# Spring_Schematic_r1_1_easyeda.net
KiCad netlist of a schematic drawn in EasyEDA
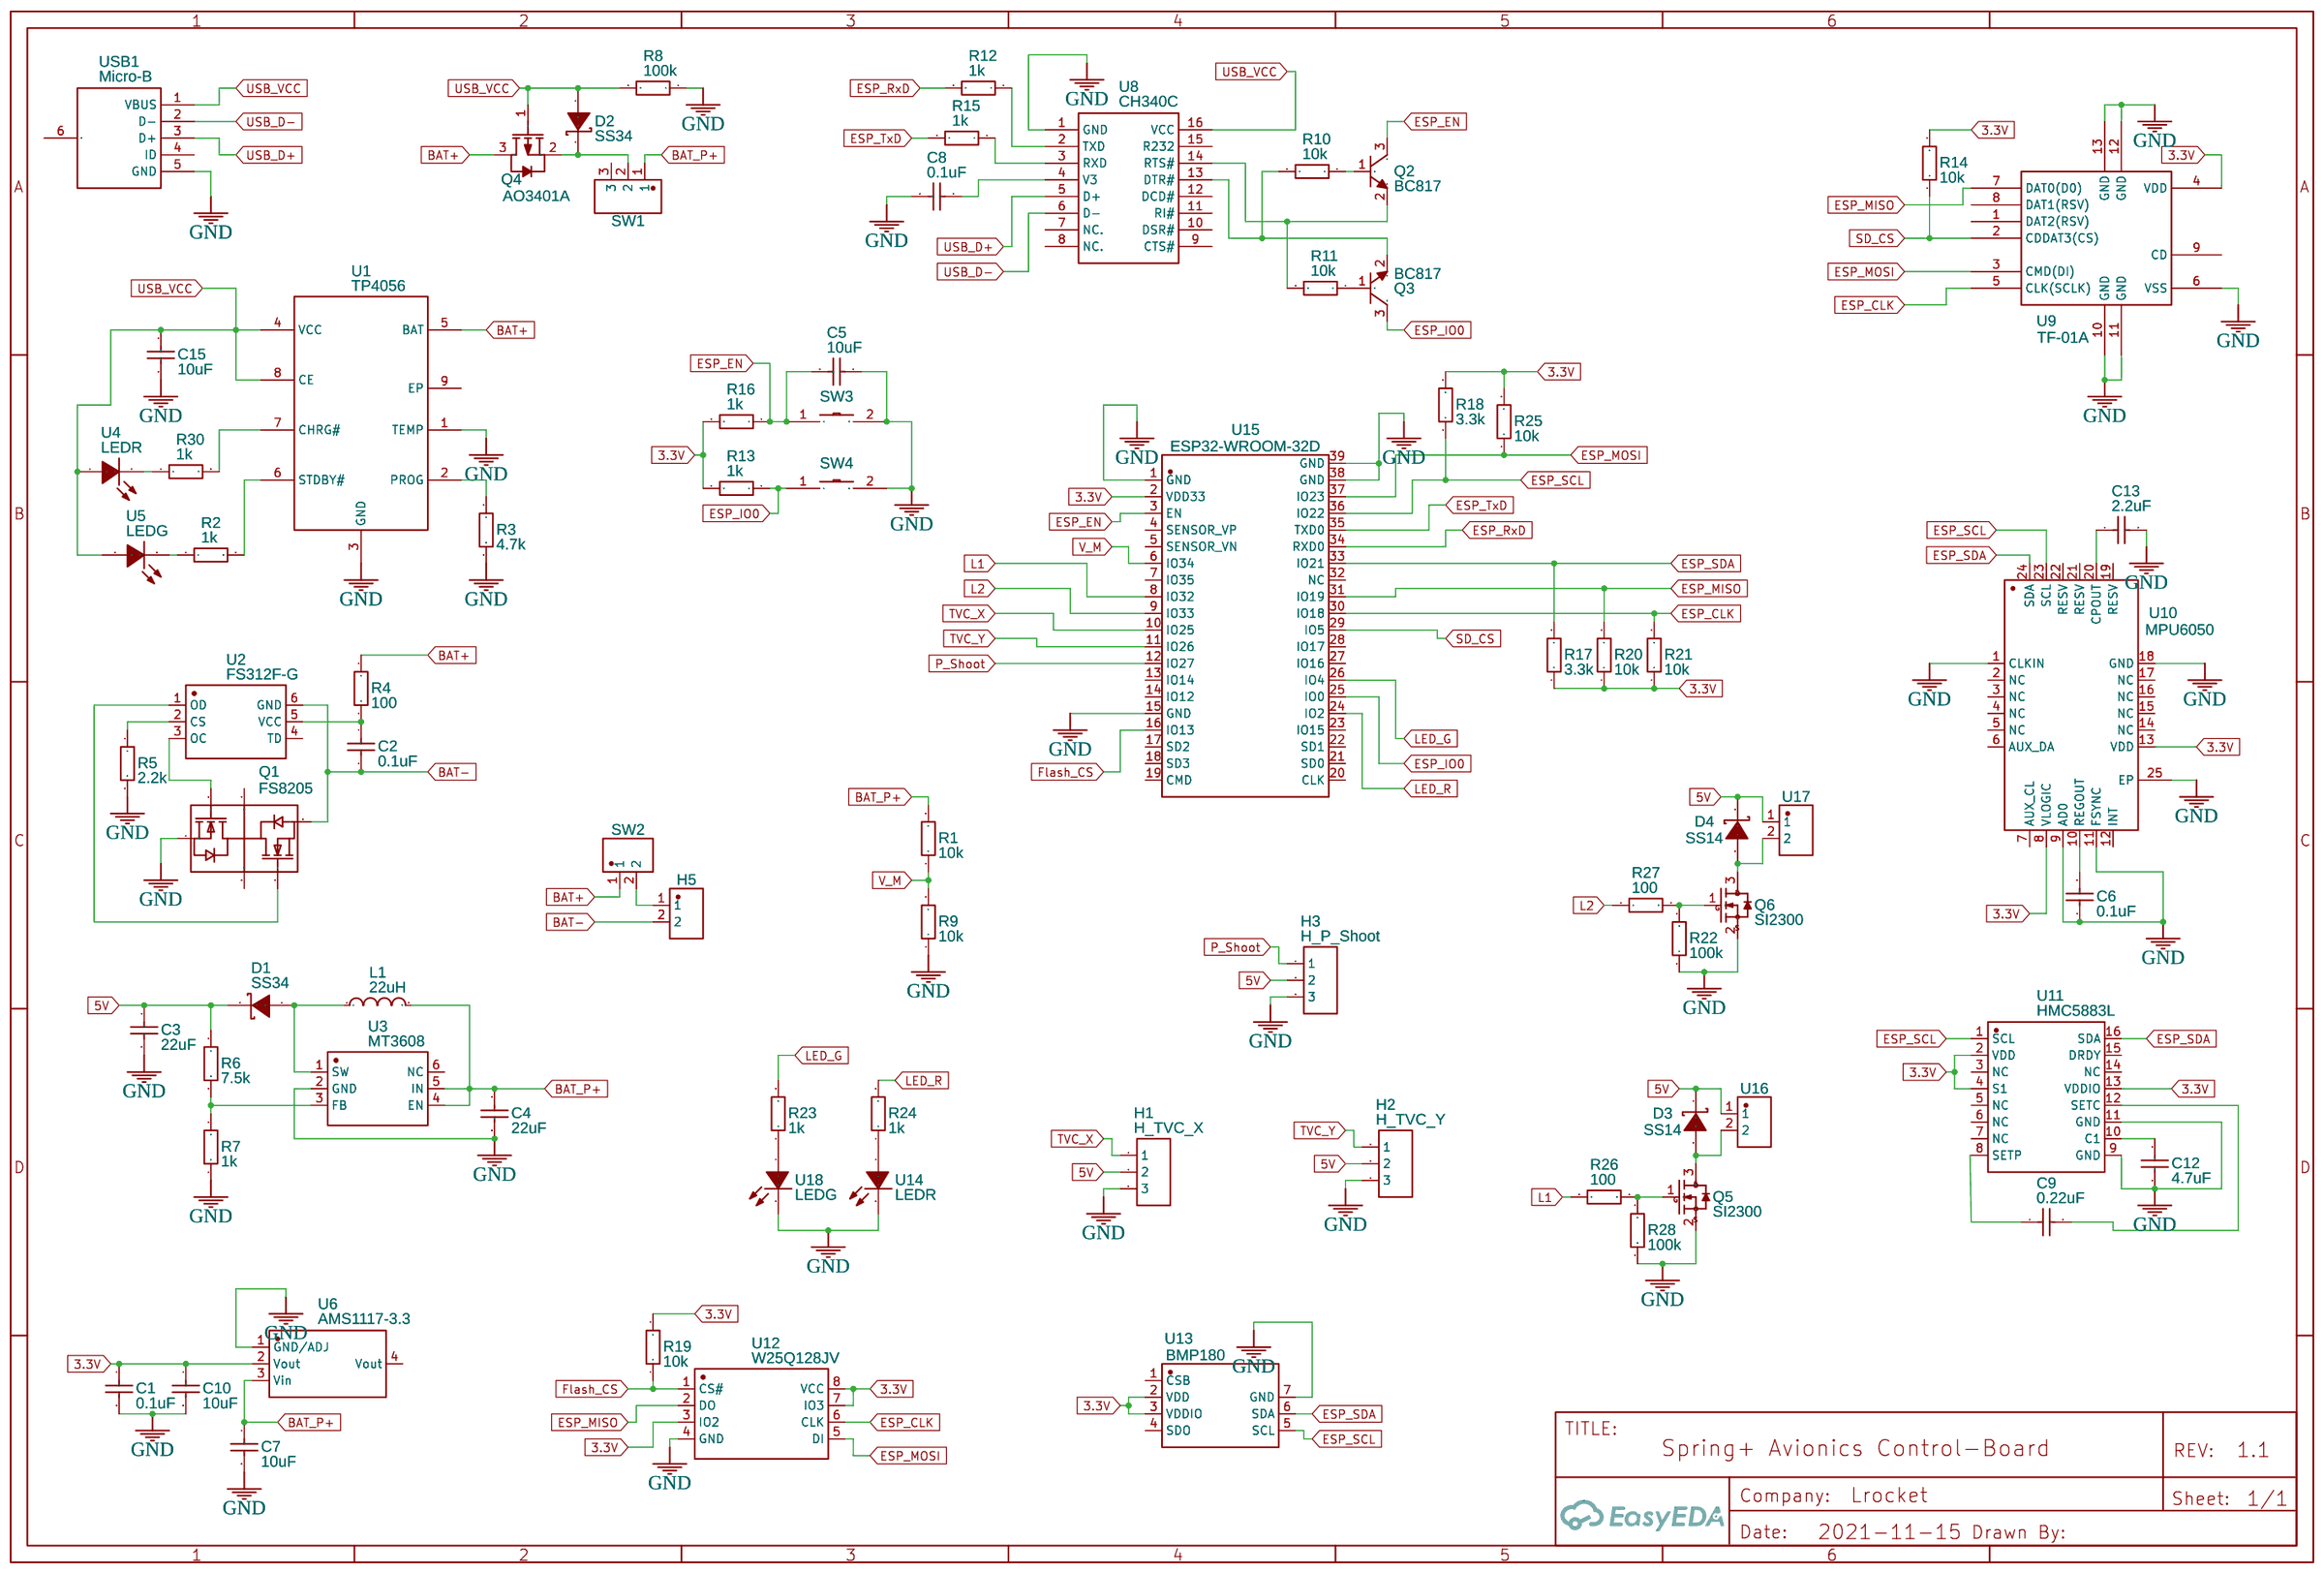
[diagram p0: schematic sheet]

(export (version "E")
  (design (tool "Eeschema 10.0.6"))
  (components
    (comp (ref "C1")
      (value "0.1uF")
      (fields
        (field (name "BOM_Manufacturer Part") "CC0603KRX7R9BB103")
        (field (name "BOM_Supplier Part") "C100042")
      )
      (libsource (lib "") (part "CC0603KRX7R9BB103"))
    )
    (comp (ref "C2")
      (value "0.1uF")
      (fields
        (field (name "BOM_Manufacturer Part") "CC0603KRX7R9BB103")
        (field (name "BOM_Supplier Part") "C100042")
      )
      (libsource (lib "") (part "CC0603KRX7R9BB103"))
    )
    (comp (ref "C3")
      (value "22uF")
      (fields
        (field (name "BOM_Manufacturer Part") "CC0603KRX7R9BB103")
        (field (name "BOM_Supplier Part") "C100042")
      )
      (libsource (lib "") (part "CC0603KRX7R9BB103"))
    )
    (comp (ref "C4")
      (value "22uF")
      (fields
        (field (name "BOM_Manufacturer Part") "CC0603KRX7R9BB103")
        (field (name "BOM_Supplier Part") "C100042")
      )
      (libsource (lib "") (part "CC0603KRX7R9BB103"))
    )
    (comp (ref "C5")
      (value "10uF")
      (fields
        (field (name "BOM_Manufacturer Part") "CC0603KRX7R9BB103")
        (field (name "BOM_Supplier Part") "C100042")
      )
      (libsource (lib "") (part "CC0603KRX7R9BB103_1"))
    )
    (comp (ref "C6")
      (value "0.1uF")
      (fields
        (field (name "BOM_Manufacturer Part") "CC0603KRX7R9BB103")
        (field (name "BOM_Supplier Part") "C100042")
      )
      (libsource (lib "") (part "CC0603KRX7R9BB103_3"))
    )
    (comp (ref "C7")
      (value "10uF")
      (fields
        (field (name "BOM_Manufacturer Part") "CC0603KRX7R9BB103")
        (field (name "BOM_Supplier Part") "C100042")
      )
      (libsource (lib "") (part "CC0603KRX7R9BB103"))
    )
    (comp (ref "C8")
      (value "0.1uF")
      (fields
        (field (name "BOM_Manufacturer Part") "CC0603KRX7R9BB103")
        (field (name "BOM_Supplier Part") "C100042")
      )
      (libsource (lib "") (part "CC0603KRX7R9BB103_1"))
    )
    (comp (ref "C9")
      (value "0.22uF")
      (fields
        (field (name "BOM_Manufacturer Part") "CC0603KRX7R9BB103")
        (field (name "BOM_Supplier Part") "C100042")
      )
      (libsource (lib "") (part "CC0603KRX7R9BB103_2"))
    )
    (comp (ref "C10")
      (value "10uF")
      (fields
        (field (name "BOM_Manufacturer Part") "CC0603KRX7R9BB103")
        (field (name "BOM_Supplier Part") "C100042")
      )
      (libsource (lib "") (part "CC0603KRX7R9BB103"))
    )
    (comp (ref "C12")
      (value "4.7uF")
      (fields
        (field (name "BOM_Manufacturer Part") "CC0603KRX7R9BB103")
        (field (name "BOM_Supplier Part") "C100042")
      )
      (libsource (lib "") (part "CC0603KRX7R9BB103"))
    )
    (comp (ref "C13")
      (value "2.2uF")
      (fields
        (field (name "BOM_Manufacturer Part") "CC0603KRX7R9BB103")
        (field (name "BOM_Supplier Part") "C100042")
      )
      (libsource (lib "") (part "CC0603KRX7R9BB103_2"))
    )
    (comp (ref "C15")
      (value "10uF")
      (fields
        (field (name "BOM_Manufacturer Part") "CC0603KRX7R9BB103")
        (field (name "BOM_Supplier Part") "C100042")
      )
      (libsource (lib "") (part "CC0603KRX7R9BB103"))
    )
    (comp (ref "D1")
      (value "SS34")
      (fields (field (name "BOM_Supplier Part") "C13763"))
      (libsource (lib "") (part "SS34_1"))
    )
    (comp (ref "D2")
      (value "SS34")
      (fields (field (name "BOM_Supplier Part") "C13763"))
      (libsource (lib "") (part "SS34"))
    )
    (comp (ref "D3")
      (value "SS14")
      (fields (field (name "BOM_Supplier Part") "C2480"))
      (libsource (lib "") (part "SS14"))
    )
    (comp (ref "D4")
      (value "SS14")
      (fields (field (name "BOM_Supplier Part") "C2480"))
      (libsource (lib "") (part "SS14"))
    )
    (comp (ref "H1")
      (value "H_TVC_X")
      (fields
        (field (name "BOM_Manufacturer Part") "Header2.54mm 1*3P")
        (field (name "BOM_Supplier Part") "C49257")
      )
      (libsource (lib "") (part "Header-Male-2.54_1x3"))
    )
    (comp (ref "H2")
      (value "H_TVC_Y")
      (fields
        (field (name "BOM_Manufacturer Part") "Header2.54mm 1*3P")
        (field (name "BOM_Supplier Part") "C49257")
      )
      (libsource (lib "") (part "Header-Male-2.54_1x3"))
    )
    (comp (ref "H3")
      (value "H_P_Shoot")
      (fields
        (field (name "BOM_Manufacturer Part") "Header2.54mm 1*3P")
        (field (name "BOM_Supplier Part") "C49257")
      )
      (libsource (lib "") (part "Header-Male-2.54_1x3"))
    )
    (comp (ref "H5")
      (value "22-28-4020")
      (fields (field (name "BOM_Supplier Part") "C234182"))
      (libsource (lib "") (part "22-28-4020"))
    )
    (comp (ref "L1")
      (value "22uH")
      (fields
        (field (name "BOM_Manufacturer Part") "FXL0630-220-M")
        (field (name "BOM_Supplier Part") "C177244")
      )
      (libsource (lib "") (part "FXL0630-220-M"))
    )
    (comp (ref "Q1")
      (value "FS8205")
      (fields (field (name "BOM_Supplier Part") "C32254"))
      (libsource (lib "") (part "FS8205"))
    )
    (comp (ref "Q2")
      (value "BC817")
      (fields (field (name "BOM_Manufacturer Part") "BC817-25") (field (name "BOM_Supplier Part") "C8588"))
      (libsource (lib "") (part "BC817-25"))
    )
    (comp (ref "Q3")
      (value "BC817")
      (fields (field (name "BOM_Manufacturer Part") "BC817-25") (field (name "BOM_Supplier Part") "C8588"))
      (libsource (lib "") (part "BC817-25_1"))
    )
    (comp (ref "Q4")
      (value "AO3401A")
      (fields (field (name "BOM_Supplier Part") "C15127"))
      (libsource (lib "") (part "AO3401A"))
    )
    (comp (ref "Q5")
      (value "SI2300")
      (fields (field (name "BOM_Supplier Part") "C181085"))
      (libsource (lib "") (part "SI2300"))
    )
    (comp (ref "Q6")
      (value "SI2300")
      (fields (field (name "BOM_Supplier Part") "C181085"))
      (libsource (lib "") (part "SI2300"))
    )
    (comp (ref "R1")
      (value "10k")
      (fields
        (field (name "BOM_Manufacturer Part") "TR0603B10KP05250.1W")
        (field (name "BOM_Supplier Part") "C188363")
      )
      (libsource (lib "") (part "TR0603B10KP05250.1W"))
    )
    (comp (ref "R2")
      (value "1k")
      (fields
        (field (name "BOM_Manufacturer Part") "TR0603B10KP05250.1W")
        (field (name "BOM_Supplier Part") "C188363")
      )
      (libsource (lib "") (part "TR0603B10KP05250.1W_1"))
    )
    (comp (ref "R3")
      (value "4.7k")
      (fields
        (field (name "BOM_Manufacturer Part") "TR0603B10KP05250.1W")
        (field (name "BOM_Supplier Part") "C188363")
      )
      (libsource (lib "") (part "TR0603B10KP05250.1W_3"))
    )
    (comp (ref "R4")
      (value "100")
      (fields
        (field (name "BOM_Manufacturer Part") "TR0603B10KP05250.1W")
        (field (name "BOM_Supplier Part") "C188363")
      )
      (libsource (lib "") (part "TR0603B10KP05250.1W_3"))
    )
    (comp (ref "R5")
      (value "2.2k")
      (fields
        (field (name "BOM_Manufacturer Part") "TR0603B10KP05250.1W")
        (field (name "BOM_Supplier Part") "C188363")
      )
      (libsource (lib "") (part "TR0603B10KP05250.1W_3"))
    )
    (comp (ref "R6")
      (value "7.5k")
      (fields
        (field (name "BOM_Manufacturer Part") "TR0603B10KP05250.1W")
        (field (name "BOM_Supplier Part") "C188363")
      )
      (libsource (lib "") (part "TR0603B10KP05250.1W_3"))
    )
    (comp (ref "R7")
      (value "1k")
      (fields
        (field (name "BOM_Manufacturer Part") "TR0603B10KP05250.1W")
        (field (name "BOM_Supplier Part") "C188363")
      )
      (libsource (lib "") (part "TR0603B10KP05250.1W_3"))
    )
    (comp (ref "R8")
      (value "100k")
      (fields
        (field (name "BOM_Manufacturer Part") "TR0603B10KP05250.1W")
        (field (name "BOM_Supplier Part") "C188363")
      )
      (libsource (lib "") (part "TR0603B10KP05250.1W_2"))
    )
    (comp (ref "R9")
      (value "10k")
      (fields
        (field (name "BOM_Manufacturer Part") "TR0603B10KP05250.1W")
        (field (name "BOM_Supplier Part") "C188363")
      )
      (libsource (lib "") (part "TR0603B10KP05250.1W"))
    )
    (comp (ref "R10")
      (value "10k")
      (fields
        (field (name "BOM_Manufacturer Part") "TR0603B10KP05250.1W")
        (field (name "BOM_Supplier Part") "C188363")
      )
      (libsource (lib "") (part "TR0603B10KP05250.1W_2"))
    )
    (comp (ref "R11")
      (value "10k")
      (fields
        (field (name "BOM_Manufacturer Part") "TR0603B10KP05250.1W")
        (field (name "BOM_Supplier Part") "C188363")
      )
      (libsource (lib "") (part "TR0603B10KP05250.1W_2"))
    )
    (comp (ref "R12")
      (value "1k")
      (fields
        (field (name "BOM_Manufacturer Part") "TR0603B10KP05250.1W")
        (field (name "BOM_Supplier Part") "C188363")
      )
      (libsource (lib "") (part "TR0603B10KP05250.1W_2"))
    )
    (comp (ref "R13")
      (value "1k")
      (fields
        (field (name "BOM_Manufacturer Part") "TR0603B10KP05250.1W")
        (field (name "BOM_Supplier Part") "C188363")
      )
      (libsource (lib "") (part "TR0603B10KP05250.1W_2"))
    )
    (comp (ref "R14")
      (value "10k")
      (fields
        (field (name "BOM_Manufacturer Part") "TR0603B10KP05250.1W")
        (field (name "BOM_Supplier Part") "C188363")
      )
      (libsource (lib "") (part "TR0603B10KP05250.1W"))
    )
    (comp (ref "R15")
      (value "1k")
      (fields
        (field (name "BOM_Manufacturer Part") "TR0603B10KP05250.1W")
        (field (name "BOM_Supplier Part") "C188363")
      )
      (libsource (lib "") (part "TR0603B10KP05250.1W_2"))
    )
    (comp (ref "R16")
      (value "1k")
      (fields
        (field (name "BOM_Manufacturer Part") "TR0603B10KP05250.1W")
        (field (name "BOM_Supplier Part") "C188363")
      )
      (libsource (lib "") (part "TR0603B10KP05250.1W_2"))
    )
    (comp (ref "R17")
      (value "3.3k")
      (fields
        (field (name "BOM_Manufacturer Part") "TR0603B10KP05250.1W")
        (field (name "BOM_Supplier Part") "C188363")
      )
      (libsource (lib "") (part "TR0603B10KP05250.1W"))
    )
    (comp (ref "R18")
      (value "3.3k")
      (fields
        (field (name "BOM_Manufacturer Part") "TR0603B10KP05250.1W")
        (field (name "BOM_Supplier Part") "C188363")
      )
      (libsource (lib "") (part "TR0603B10KP05250.1W"))
    )
    (comp (ref "R19")
      (value "10k")
      (fields
        (field (name "BOM_Manufacturer Part") "TR0603B10KP05250.1W")
        (field (name "BOM_Supplier Part") "C188363")
      )
      (libsource (lib "") (part "TR0603B10KP05250.1W"))
    )
    (comp (ref "R20")
      (value "10k")
      (fields
        (field (name "BOM_Manufacturer Part") "TR0603B10KP05250.1W")
        (field (name "BOM_Supplier Part") "C188363")
      )
      (libsource (lib "") (part "TR0603B10KP05250.1W"))
    )
    (comp (ref "R21")
      (value "10k")
      (fields
        (field (name "BOM_Manufacturer Part") "TR0603B10KP05250.1W")
        (field (name "BOM_Supplier Part") "C188363")
      )
      (libsource (lib "") (part "TR0603B10KP05250.1W"))
    )
    (comp (ref "R22")
      (value "100k")
      (fields
        (field (name "BOM_Manufacturer Part") "TR0603B10KP05250.1W")
        (field (name "BOM_Supplier Part") "C188363")
      )
      (libsource (lib "") (part "TR0603B10KP05250.1W"))
    )
    (comp (ref "R23")
      (value "1k")
      (fields
        (field (name "BOM_Manufacturer Part") "TR0603B10KP05250.1W")
        (field (name "BOM_Supplier Part") "C188363")
      )
      (libsource (lib "") (part "TR0603B10KP05250.1W"))
    )
    (comp (ref "R24")
      (value "1k")
      (fields
        (field (name "BOM_Manufacturer Part") "TR0603B10KP05250.1W")
        (field (name "BOM_Supplier Part") "C188363")
      )
      (libsource (lib "") (part "TR0603B10KP05250.1W"))
    )
    (comp (ref "R25")
      (value "10k")
      (fields
        (field (name "BOM_Manufacturer Part") "TR0603B10KP05250.1W")
        (field (name "BOM_Supplier Part") "C188363")
      )
      (libsource (lib "") (part "TR0603B10KP05250.1W"))
    )
    (comp (ref "R26")
      (value "100")
      (fields
        (field (name "BOM_Manufacturer Part") "TR0603B10KP05250.1W")
        (field (name "BOM_Supplier Part") "C188363")
      )
      (libsource (lib "") (part "TR0603B10KP05250.1W_1"))
    )
    (comp (ref "R27")
      (value "100")
      (fields
        (field (name "BOM_Manufacturer Part") "TR0603B10KP05250.1W")
        (field (name "BOM_Supplier Part") "C188363")
      )
      (libsource (lib "") (part "TR0603B10KP05250.1W_1"))
    )
    (comp (ref "R28")
      (value "100k")
      (fields
        (field (name "BOM_Manufacturer Part") "TR0603B10KP05250.1W")
        (field (name "BOM_Supplier Part") "C188363")
      )
      (libsource (lib "") (part "TR0603B10KP05250.1W"))
    )
    (comp (ref "R30")
      (value "1k")
      (fields
        (field (name "BOM_Manufacturer Part") "TR0603B10KP05250.1W")
        (field (name "BOM_Supplier Part") "C188363")
      )
      (libsource (lib "") (part "TR0603B10KP05250.1W_1"))
    )
    (comp (ref "SW1")
      (value "X6511WV-03H-C30D60")
      (fields (field (name "BOM_Supplier Part") "C706875"))
      (libsource (lib "") (part "X6511WV-03H-C30D60"))
    )
    (comp (ref "SW2")
      (value "22-28-4020")
      (fields (field (name "BOM_Supplier Part") "C234182"))
      (libsource (lib "") (part "22-28-4020_1"))
    )
    (comp (ref "SW3")
      (value "TS-1101-C-W")
      (fields (field (name "BOM_Supplier Part") "C318938"))
      (libsource (lib "") (part "TS-1101-C-W"))
    )
    (comp (ref "SW4")
      (value "TS-1101-C-W")
      (fields (field (name "BOM_Supplier Part") "C318938"))
      (libsource (lib "") (part "TS-1101-C-W"))
    )
    (comp (ref "U1")
      (value "TP4056")
      (fields (field (name "BOM_Supplier Part") "C16581"))
      (libsource (lib "") (part "TP4056"))
    )
    (comp (ref "U2")
      (value "FS312F-G")
      (fields (field (name "BOM_Supplier Part") "C82736"))
      (libsource (lib "") (part "FS312F-G"))
    )
    (comp (ref "U3")
      (value "MT3608")
      (fields (field (name "BOM_Supplier Part") "C84817"))
      (libsource (lib "") (part "MT3608"))
    )
    (comp (ref "U4")
      (value "LEDR")
      (fields (field (name "BOM_Manufacturer Part") "SZYY0603W") (field (name "BOM_Supplier Part") "C434422"))
      (libsource (lib "") (part "SZYY0603W_1"))
    )
    (comp (ref "U5")
      (value "LEDG")
      (fields (field (name "BOM_Manufacturer Part") "SZYY0603W") (field (name "BOM_Supplier Part") "C434422"))
      (libsource (lib "") (part "SZYY0603W_1"))
    )
    (comp (ref "U6")
      (value "AMS1117-3.3")
      (fields (field (name "BOM_Supplier Part") "C6186"))
      (libsource (lib "") (part "AMS1117-3.3"))
    )
    (comp (ref "U8")
      (value "CH340C")
      (fields (field (name "BOM_Supplier Part") "C84681"))
      (libsource (lib "") (part "CH340C"))
    )
    (comp (ref "U9")
      (value "TF-01A")
      (fields (field (name "BOM_Supplier Part") "C91145"))
      (libsource (lib "") (part "TF-01A"))
    )
    (comp (ref "U10")
      (value "MPU6050")
      (fields
        (field (name "BOM_Manufacturer Part") "MPU6050-YJLTY")
        (field (name "BOM_Supplier Part") "C2912107")
      )
      (libsource (lib "") (part "MPU6050-YJLTY"))
    )
    (comp (ref "U11")
      (value "HMC5883L")
      (fields (field (name "BOM_Supplier Part") "C2859540"))
      (libsource (lib "") (part "HMC5883L"))
    )
    (comp (ref "U12")
      (value "W25Q128JV")
      (fields
        (field (name "BOM_Manufacturer Part") "W25Q128JVSIQTR")
        (field (name "BOM_Supplier Part") "C97521")
      )
      (libsource (lib "") (part "W25Q128JVSIQTR"))
    )
    (comp (ref "U13")
      (value "BMP180")
      (fields (field (name "BOM_Supplier Part") "C438474"))
      (libsource (lib "") (part "BMP180"))
    )
    (comp (ref "U14")
      (value "LEDR")
      (fields (field (name "BOM_Manufacturer Part") "SZYY0603W") (field (name "BOM_Supplier Part") "C434422"))
      (libsource (lib "") (part "SZYY0603W"))
    )
    (comp (ref "U15")
      (value "ESP32-WROOM-32D")
      (fields (field (name "BOM_Supplier Part") "C473012"))
      (libsource (lib "") (part "ESP32-WROOM-32D"))
    )
    (comp (ref "U16")
      (value "KF128-5.08-2P")
      (fields (field (name "BOM_Supplier Part") "C474952"))
      (libsource (lib "") (part "KF128-5.08-2P"))
    )
    (comp (ref "U17")
      (value "KF128-5.08-2P")
      (fields (field (name "BOM_Supplier Part") "C474952"))
      (libsource (lib "") (part "KF128-5.08-2P"))
    )
    (comp (ref "U18")
      (value "LEDG")
      (fields (field (name "BOM_Manufacturer Part") "SZYY0603W") (field (name "BOM_Supplier Part") "C434422"))
      (libsource (lib "") (part "SZYY0603W"))
    )
    (comp (ref "USB1")
      (value "Micro-B")
      (fields
        (field (name "BOM_Manufacturer Part") "U254-051T-4BH83-S1S")
        (field (name "BOM_Supplier Part") "C319160")
      )
      (libsource (lib "") (part "U254-051T-4BH83-S1S"))
    )
  )
  (nets
    (net (code "1") (name "3.3V") (class "Default")
      (node (ref "C1") (pin "1") (pinfunction "1_1") (pintype "input"))
      (node (ref "C10") (pin "1") (pinfunction "1_1") (pintype "input"))
      (node (ref "R13") (pin "2") (pinfunction "2_2") (pintype "unspecified"))
      (node (ref "R14") (pin "2") (pinfunction "2_2") (pintype "unspecified"))
      (node (ref "R16") (pin "2") (pinfunction "2_2") (pintype "unspecified"))
      (node (ref "R17") (pin "1") (pinfunction "1_1") (pintype "unspecified"))
      (node (ref "R18") (pin "2") (pinfunction "2_2") (pintype "unspecified"))
      (node (ref "R19") (pin "2") (pinfunction "2_2") (pintype "unspecified"))
      (node (ref "R20") (pin "1") (pinfunction "1_1") (pintype "unspecified"))
      (node (ref "R21") (pin "1") (pinfunction "1_1") (pintype "unspecified"))
      (node (ref "R25") (pin "2") (pinfunction "2_2") (pintype "unspecified"))
      (node (ref "U10") (pin "13") (pinfunction "VDD_13") (pintype "unspecified"))
      (node (ref "U10") (pin "8") (pinfunction "VLOGIC_8") (pintype "unspecified"))
      (node (ref "U11") (pin "13") (pinfunction "VDDIO_13") (pintype "unspecified"))
      (node (ref "U11") (pin "2") (pinfunction "VDD_2") (pintype "unspecified"))
      (node (ref "U11") (pin "4") (pinfunction "S1_4") (pintype "unspecified"))
      (node (ref "U12") (pin "3") (pinfunction "IO2_3") (pintype "unspecified"))
      (node (ref "U12") (pin "7") (pinfunction "IO3_7") (pintype "unspecified"))
      (node (ref "U12") (pin "8") (pinfunction "VCC_8") (pintype "unspecified"))
      (node (ref "U13") (pin "2") (pinfunction "VDD_2") (pintype "unspecified"))
      (node (ref "U13") (pin "3") (pinfunction "VDDIO_3") (pintype "unspecified"))
      (node (ref "U15") (pin "2") (pinfunction "VDD33_2") (pintype "unspecified"))
      (node (ref "U6") (pin "2") (pinfunction "Vout_2") (pintype "unspecified"))
      (node (ref "U9") (pin "4") (pinfunction "VDD_4") (pintype "input"))
    )
    (net (code "2") (name "5V") (class "Default")
      (node (ref "C3") (pin "1") (pinfunction "1_1") (pintype "input"))
      (node (ref "D1") (pin "2") (pinfunction "K_2") (pintype "unspecified"))
      (node (ref "D3") (pin "1") (pinfunction "K_1") (pintype "unspecified"))
      (node (ref "D4") (pin "1") (pinfunction "K_1") (pintype "unspecified"))
      (node (ref "H1") (pin "2") (pinfunction "2_2") (pintype "input"))
      (node (ref "H2") (pin "2") (pinfunction "2_2") (pintype "input"))
      (node (ref "H3") (pin "2") (pinfunction "2_2") (pintype "input"))
      (node (ref "R6") (pin "1") (pinfunction "1_1") (pintype "unspecified"))
      (node (ref "U16") (pin "1") (pinfunction "1_1") (pintype "unspecified"))
      (node (ref "U17") (pin "1") (pinfunction "1_1") (pintype "unspecified"))
    )
    (net (code "3") (name "BAT+") (class "Default")
      (node (ref "Q4") (pin "3") (pinfunction "D_3") (pintype "unspecified"))
      (node (ref "R4") (pin "1") (pinfunction "1_1") (pintype "unspecified"))
      (node (ref "SW2") (pin "1") (pinfunction "1_1") (pintype "unspecified"))
      (node (ref "U1") (pin "5") (pinfunction "BAT_5") (pintype "unspecified"))
    )
    (net (code "4") (name "BAT-") (class "Default")
      (node (ref "C2") (pin "2") (pinfunction "2_2") (pintype "input"))
      (node (ref "H5") (pin "2") (pinfunction "2_2") (pintype "unspecified"))
      (node (ref "Q1") (pin "3") (pinfunction "S2_3") (pintype "unspecified"))
      (node (ref "U2") (pin "6") (pinfunction "GND_6") (pintype "unspecified"))
    )
    (net (code "5") (name "BAT_P+") (class "Default")
      (node (ref "C4") (pin "1") (pinfunction "1_1") (pintype "input"))
      (node (ref "C7") (pin "1") (pinfunction "1_1") (pintype "input"))
      (node (ref "L1") (pin "2") (pinfunction "2_2") (pintype "unspecified"))
      (node (ref "R1") (pin "2") (pinfunction "2_2") (pintype "unspecified"))
      (node (ref "SW1") (pin "1") (pinfunction "1_1") (pintype "unspecified"))
      (node (ref "U3") (pin "4") (pinfunction "EN_4") (pintype "unspecified"))
      (node (ref "U3") (pin "5") (pinfunction "IN_5") (pintype "unspecified"))
      (node (ref "U6") (pin "3") (pinfunction "Vin_3") (pintype "unspecified"))
    )
    (net (code "6") (name "ESP_CLK") (class "Default")
      (node (ref "R21") (pin "2") (pinfunction "2_2") (pintype "unspecified"))
      (node (ref "U12") (pin "6") (pinfunction "CLK_6") (pintype "unspecified"))
      (node (ref "U15") (pin "30") (pinfunction "IO18_30") (pintype "unspecified"))
      (node (ref "U9") (pin "5") (pinfunction "CLK(SCLK)_5") (pintype "input"))
    )
    (net (code "7") (name "ESP_EN") (class "Default")
      (node (ref "C5") (pin "2") (pinfunction "2_2") (pintype "input"))
      (node (ref "Q2") (pin "3") (pinfunction "C_3") (pintype "unspecified"))
      (node (ref "R16") (pin "1") (pinfunction "1_1") (pintype "unspecified"))
      (node (ref "SW3") (pin "1") (pinfunction "1_1") (pintype "unspecified"))
      (node (ref "U15") (pin "3") (pinfunction "EN_3") (pintype "unspecified"))
    )
    (net (code "8") (name "ESP_IO0") (class "Default")
      (node (ref "Q3") (pin "3") (pinfunction "C_3") (pintype "unspecified"))
      (node (ref "R13") (pin "1") (pinfunction "1_1") (pintype "unspecified"))
      (node (ref "SW4") (pin "1") (pinfunction "1_1") (pintype "unspecified"))
      (node (ref "U15") (pin "25") (pinfunction "IO0_25") (pintype "unspecified"))
    )
    (net (code "9") (name "ESP_MISO") (class "Default")
      (node (ref "R20") (pin "2") (pinfunction "2_2") (pintype "unspecified"))
      (node (ref "U12") (pin "2") (pinfunction "DO_2") (pintype "unspecified"))
      (node (ref "U15") (pin "31") (pinfunction "IO19_31") (pintype "unspecified"))
      (node (ref "U9") (pin "7") (pinfunction "DAT0(D0)_7") (pintype "bidirectional"))
    )
    (net (code "10") (name "ESP_MOSI") (class "Default")
      (node (ref "R25") (pin "1") (pinfunction "1_1") (pintype "unspecified"))
      (node (ref "U12") (pin "5") (pinfunction "DI_5") (pintype "unspecified"))
      (node (ref "U15") (pin "37") (pinfunction "IO23_37") (pintype "unspecified"))
      (node (ref "U9") (pin "3") (pinfunction "CMD(DI)_3") (pintype "input"))
    )
    (net (code "11") (name "ESP_RxD") (class "Default")
      (node (ref "R12") (pin "2") (pinfunction "2_2") (pintype "unspecified"))
      (node (ref "U15") (pin "34") (pinfunction "RXD0_34") (pintype "unspecified"))
    )
    (net (code "12") (name "ESP_SCL") (class "Default")
      (node (ref "R18") (pin "1") (pinfunction "1_1") (pintype "unspecified"))
      (node (ref "U10") (pin "23") (pinfunction "SCL_23") (pintype "unspecified"))
      (node (ref "U11") (pin "1") (pinfunction "SCL_1") (pintype "unspecified"))
      (node (ref "U13") (pin "5") (pinfunction "SCL_5") (pintype "unspecified"))
      (node (ref "U15") (pin "36") (pinfunction "IO22_36") (pintype "unspecified"))
    )
    (net (code "13") (name "ESP_SDA") (class "Default")
      (node (ref "R17") (pin "2") (pinfunction "2_2") (pintype "unspecified"))
      (node (ref "U10") (pin "24") (pinfunction "SDA_24") (pintype "unspecified"))
      (node (ref "U11") (pin "16") (pinfunction "SDA_16") (pintype "unspecified"))
      (node (ref "U13") (pin "6") (pinfunction "SDA_6") (pintype "unspecified"))
      (node (ref "U15") (pin "33") (pinfunction "IO21_33") (pintype "unspecified"))
    )
    (net (code "14") (name "ESP_TxD") (class "Default")
      (node (ref "R15") (pin "2") (pinfunction "2_2") (pintype "unspecified"))
      (node (ref "U15") (pin "35") (pinfunction "TXD0_35") (pintype "unspecified"))
    )
    (net (code "15") (name "Flash_CS") (class "Default")
      (node (ref "R19") (pin "1") (pinfunction "1_1") (pintype "unspecified"))
      (node (ref "U12") (pin "1") (pinfunction "CS#_1") (pintype "unspecified"))
      (node (ref "U15") (pin "16") (pinfunction "IO13_16") (pintype "unspecified"))
    )
    (net (code "16") (name "GND") (class "Default")
      (node (ref "C1") (pin "2") (pinfunction "2_2") (pintype "input"))
      (node (ref "C10") (pin "2") (pinfunction "2_2") (pintype "input"))
      (node (ref "C12") (pin "2") (pinfunction "2_2") (pintype "input"))
      (node (ref "C13") (pin "2") (pinfunction "2_2") (pintype "input"))
      (node (ref "C15") (pin "2") (pinfunction "2_2") (pintype "input"))
      (node (ref "C3") (pin "2") (pinfunction "2_2") (pintype "input"))
      (node (ref "C4") (pin "2") (pinfunction "2_2") (pintype "input"))
      (node (ref "C5") (pin "1") (pinfunction "1_1") (pintype "input"))
      (node (ref "C6") (pin "1") (pinfunction "1_1") (pintype "input"))
      (node (ref "C7") (pin "2") (pinfunction "2_2") (pintype "input"))
      (node (ref "C8") (pin "2") (pinfunction "2_2") (pintype "input"))
      (node (ref "H1") (pin "3") (pinfunction "3_3") (pintype "input"))
      (node (ref "H2") (pin "3") (pinfunction "3_3") (pintype "input"))
      (node (ref "H3") (pin "3") (pinfunction "3_3") (pintype "input"))
      (node (ref "Q1") (pin "1") (pinfunction "S1_1") (pintype "unspecified"))
      (node (ref "Q5") (pin "2") (pinfunction "S_2") (pintype "unspecified"))
      (node (ref "Q6") (pin "2") (pinfunction "S_2") (pintype "unspecified"))
      (node (ref "R22") (pin "1") (pinfunction "1_1") (pintype "unspecified"))
      (node (ref "R28") (pin "1") (pinfunction "1_1") (pintype "unspecified"))
      (node (ref "R3") (pin "2") (pinfunction "2_2") (pintype "unspecified"))
      (node (ref "R5") (pin "2") (pinfunction "2_2") (pintype "unspecified"))
      (node (ref "R7") (pin "2") (pinfunction "2_2") (pintype "unspecified"))
      (node (ref "R8") (pin "1") (pinfunction "1_1") (pintype "unspecified"))
      (node (ref "R9") (pin "1") (pinfunction "1_1") (pintype "unspecified"))
      (node (ref "SW3") (pin "2") (pinfunction "2_2") (pintype "unspecified"))
      (node (ref "SW4") (pin "2") (pinfunction "2_2") (pintype "unspecified"))
      (node (ref "U1") (pin "1") (pinfunction "TEMP_1") (pintype "unspecified"))
      (node (ref "U1") (pin "3") (pinfunction "GND_3") (pintype "unspecified"))
      (node (ref "U10") (pin "1") (pinfunction "CLKIN_1") (pintype "unspecified"))
      (node (ref "U10") (pin "11") (pinfunction "FSYNC_11") (pintype "unspecified"))
      (node (ref "U10") (pin "18") (pinfunction "GND_18") (pintype "unspecified"))
      (node (ref "U10") (pin "25") (pinfunction "EP_25") (pintype "unspecified"))
      (node (ref "U10") (pin "9") (pinfunction "AD0_9") (pintype "unspecified"))
      (node (ref "U11") (pin "11") (pinfunction "GND_11") (pintype "unspecified"))
      (node (ref "U11") (pin "9") (pinfunction "GND_9") (pintype "unspecified"))
      (node (ref "U12") (pin "4") (pinfunction "GND_4") (pintype "unspecified"))
      (node (ref "U13") (pin "7") (pinfunction "GND_7") (pintype "unspecified"))
      (node (ref "U14") (pin "2") (pinfunction "-_2") (pintype "unspecified"))
      (node (ref "U15") (pin "1") (pinfunction "GND_1") (pintype "unspecified"))
      (node (ref "U15") (pin "15") (pinfunction "GND_15") (pintype "unspecified"))
      (node (ref "U15") (pin "38") (pinfunction "GND_38") (pintype "unspecified"))
      (node (ref "U15") (pin "39") (pinfunction "GND_39") (pintype "unspecified"))
      (node (ref "U18") (pin "2") (pinfunction "-_2") (pintype "unspecified"))
      (node (ref "U3") (pin "2") (pinfunction "GND_2") (pintype "unspecified"))
      (node (ref "U6") (pin "1") (pinfunction "GND/ADJ_1") (pintype "unspecified"))
      (node (ref "U8") (pin "1") (pinfunction "GND_1") (pintype "unspecified"))
      (node (ref "U9") (pin "10") (pinfunction "GND_10") (pintype "input"))
      (node (ref "U9") (pin "11") (pinfunction "GND_11") (pintype "input"))
      (node (ref "U9") (pin "12") (pinfunction "GND_12") (pintype "input"))
      (node (ref "U9") (pin "13") (pinfunction "GND_13") (pintype "input"))
      (node (ref "U9") (pin "6") (pinfunction "VSS_6") (pintype "input"))
      (node (ref "USB1") (pin "5") (pinfunction "GND_5") (pintype "input"))
    )
    (net (code "17") (name "L1") (class "Default")
      (node (ref "R26") (pin "1") (pinfunction "1_1") (pintype "unspecified"))
      (node (ref "U15") (pin "8") (pinfunction "IO32_8") (pintype "unspecified"))
    )
    (net (code "18") (name "L2") (class "Default")
      (node (ref "R27") (pin "1") (pinfunction "1_1") (pintype "unspecified"))
      (node (ref "U15") (pin "9") (pinfunction "IO33_9") (pintype "unspecified"))
    )
    (net (code "19") (name "LED_G") (class "Default")
      (node (ref "R23") (pin "2") (pinfunction "2_2") (pintype "unspecified"))
      (node (ref "U15") (pin "26") (pinfunction "IO4_26") (pintype "unspecified"))
    )
    (net (code "20") (name "LED_R") (class "Default")
      (node (ref "R24") (pin "2") (pinfunction "2_2") (pintype "unspecified"))
      (node (ref "U15") (pin "24") (pinfunction "IO2_24") (pintype "unspecified"))
    )
    (net (code "21") (name "Net-(D1-A)") (class "Default")
      (node (ref "D1") (pin "1") (pinfunction "A_1") (pintype "unspecified"))
      (node (ref "L1") (pin "1") (pinfunction "1_1") (pintype "unspecified"))
      (node (ref "U3") (pin "1") (pinfunction "SW_1") (pintype "unspecified"))
    )
    (net (code "22") (name "Net-(D2-K)") (class "Default")
      (node (ref "D2") (pin "2") (pinfunction "K_2") (pintype "unspecified"))
      (node (ref "Q4") (pin "2") (pinfunction "S_2") (pintype "unspecified"))
      (node (ref "SW1") (pin "2") (pinfunction "2_2") (pintype "unspecified"))
    )
    (net (code "23") (name "Net-(D3-A)") (class "Default")
      (node (ref "D3") (pin "2") (pinfunction "A_2") (pintype "unspecified"))
      (node (ref "Q5") (pin "3") (pinfunction "D_3") (pintype "unspecified"))
      (node (ref "U16") (pin "2") (pinfunction "2_2") (pintype "unspecified"))
    )
    (net (code "24") (name "Net-(D4-A)") (class "Default")
      (node (ref "D4") (pin "2") (pinfunction "A_2") (pintype "unspecified"))
      (node (ref "Q6") (pin "3") (pinfunction "D_3") (pintype "unspecified"))
      (node (ref "U17") (pin "2") (pinfunction "2_2") (pintype "unspecified"))
    )
    (net (code "25") (name "Net-(H5-Pad1)") (class "Default")
      (node (ref "H5") (pin "1") (pinfunction "1_1") (pintype "unspecified"))
      (node (ref "SW2") (pin "2") (pinfunction "2_2") (pintype "unspecified"))
    )
    (net (code "26") (name "Net-(Q1-G1)") (class "Default")
      (node (ref "Q1") (pin "6") (pinfunction "G1_6") (pintype "unspecified"))
      (node (ref "U2") (pin "3") (pinfunction "OC_3") (pintype "unspecified"))
    )
    (net (code "27") (name "Net-(Q1-G2)") (class "Default")
      (node (ref "Q1") (pin "4") (pinfunction "G2_4") (pintype "unspecified"))
      (node (ref "U2") (pin "1") (pinfunction "OD_1") (pintype "unspecified"))
    )
    (net (code "28") (name "Net-(Q2-B)") (class "Default")
      (node (ref "Q2") (pin "1") (pinfunction "B_1") (pintype "unspecified"))
      (node (ref "R10") (pin "1") (pinfunction "1_1") (pintype "unspecified"))
    )
    (net (code "29") (name "Net-(Q2-E)") (class "Default")
      (node (ref "Q2") (pin "2") (pinfunction "E_2") (pintype "unspecified"))
      (node (ref "R11") (pin "2") (pinfunction "2_2") (pintype "unspecified"))
      (node (ref "U8") (pin "14") (pinfunction "RTS#_14") (pintype "unspecified"))
    )
    (net (code "30") (name "Net-(Q3-B)") (class "Default")
      (node (ref "Q3") (pin "1") (pinfunction "B_1") (pintype "unspecified"))
      (node (ref "R11") (pin "1") (pinfunction "1_1") (pintype "unspecified"))
    )
    (net (code "31") (name "Net-(Q3-E)") (class "Default")
      (node (ref "Q3") (pin "2") (pinfunction "E_2") (pintype "unspecified"))
      (node (ref "R10") (pin "2") (pinfunction "2_2") (pintype "unspecified"))
      (node (ref "U8") (pin "13") (pinfunction "DTR#_13") (pintype "unspecified"))
    )
    (net (code "32") (name "Net-(Q5-G)") (class "Default")
      (node (ref "Q5") (pin "1") (pinfunction "G_1") (pintype "unspecified"))
      (node (ref "R26") (pin "2") (pinfunction "2_2") (pintype "unspecified"))
      (node (ref "R28") (pin "2") (pinfunction "2_2") (pintype "unspecified"))
    )
    (net (code "33") (name "Net-(Q6-G)") (class "Default")
      (node (ref "Q6") (pin "1") (pinfunction "G_1") (pintype "unspecified"))
      (node (ref "R22") (pin "2") (pinfunction "2_2") (pintype "unspecified"))
      (node (ref "R27") (pin "2") (pinfunction "2_2") (pintype "unspecified"))
    )
    (net (code "34") (name "Net-(U1-CHRG#)") (class "Default")
      (node (ref "R30") (pin "2") (pinfunction "2_2") (pintype "unspecified"))
      (node (ref "U1") (pin "7") (pinfunction "CHRG#_7") (pintype "unspecified"))
    )
    (net (code "35") (name "Net-(U1-PROG)") (class "Default")
      (node (ref "R3") (pin "1") (pinfunction "1_1") (pintype "unspecified"))
      (node (ref "U1") (pin "2") (pinfunction "PROG_2") (pintype "unspecified"))
    )
    (net (code "36") (name "Net-(U1-STDBY#)") (class "Default")
      (node (ref "R2") (pin "2") (pinfunction "2_2") (pintype "unspecified"))
      (node (ref "U1") (pin "6") (pinfunction "STDBY#_6") (pintype "unspecified"))
    )
    (net (code "37") (name "Net-(U2-CS)") (class "Default")
      (node (ref "R5") (pin "1") (pinfunction "1_1") (pintype "unspecified"))
      (node (ref "U2") (pin "2") (pinfunction "CS_2") (pintype "unspecified"))
    )
    (net (code "38") (name "Net-(U2-VCC)") (class "Default")
      (node (ref "C2") (pin "1") (pinfunction "1_1") (pintype "input"))
      (node (ref "R4") (pin "2") (pinfunction "2_2") (pintype "unspecified"))
      (node (ref "U2") (pin "5") (pinfunction "VCC_5") (pintype "unspecified"))
    )
    (net (code "39") (name "Net-(U3-FB)") (class "Default")
      (node (ref "R6") (pin "2") (pinfunction "2_2") (pintype "unspecified"))
      (node (ref "R7") (pin "1") (pinfunction "1_1") (pintype "unspecified"))
      (node (ref "U3") (pin "3") (pinfunction "FB_3") (pintype "unspecified"))
    )
    (net (code "40") (name "Net-(U4--)") (class "Default")
      (node (ref "R30") (pin "1") (pinfunction "1_1") (pintype "unspecified"))
      (node (ref "U4") (pin "2") (pinfunction "-_2") (pintype "unspecified"))
    )
    (net (code "41") (name "Net-(U5--)") (class "Default")
      (node (ref "R2") (pin "1") (pinfunction "1_1") (pintype "unspecified"))
      (node (ref "U5") (pin "2") (pinfunction "-_2") (pintype "unspecified"))
    )
    (net (code "42") (name "Net-(U8-RXD)") (class "Default")
      (node (ref "R15") (pin "1") (pinfunction "1_1") (pintype "unspecified"))
      (node (ref "U8") (pin "3") (pinfunction "RXD_3") (pintype "unspecified"))
    )
    (net (code "43") (name "Net-(U8-TXD)") (class "Default")
      (node (ref "R12") (pin "1") (pinfunction "1_1") (pintype "unspecified"))
      (node (ref "U8") (pin "2") (pinfunction "TXD_2") (pintype "unspecified"))
    )
    (net (code "44") (name "Net-(U8-V3)") (class "Default")
      (node (ref "C8") (pin "1") (pinfunction "1_1") (pintype "input"))
      (node (ref "U8") (pin "4") (pinfunction "V3_4") (pintype "unspecified"))
    )
    (net (code "45") (name "Net-(U10-CPOUT)") (class "Default")
      (node (ref "C13") (pin "1") (pinfunction "1_1") (pintype "input"))
      (node (ref "U10") (pin "20") (pinfunction "CPOUT_20") (pintype "unspecified"))
    )
    (net (code "46") (name "Net-(U10-REGOUT)") (class "Default")
      (node (ref "C6") (pin "2") (pinfunction "2_2") (pintype "input"))
      (node (ref "U10") (pin "10") (pinfunction "REGOUT_10") (pintype "unspecified"))
    )
    (net (code "47") (name "Net-(U11-C1)") (class "Default")
      (node (ref "C12") (pin "1") (pinfunction "1_1") (pintype "input"))
      (node (ref "U11") (pin "10") (pinfunction "C1_10") (pintype "unspecified"))
    )
    (net (code "48") (name "Net-(U11-SETC)") (class "Default")
      (node (ref "C9") (pin "2") (pinfunction "2_2") (pintype "input"))
      (node (ref "U11") (pin "12") (pinfunction "SETC_12") (pintype "unspecified"))
    )
    (net (code "49") (name "Net-(U11-SETP)") (class "Default")
      (node (ref "C9") (pin "1") (pinfunction "1_1") (pintype "input"))
      (node (ref "U11") (pin "8") (pinfunction "SETP_8") (pintype "unspecified"))
    )
    (net (code "50") (name "Net-(U14-+)") (class "Default")
      (node (ref "R24") (pin "1") (pinfunction "1_1") (pintype "unspecified"))
      (node (ref "U14") (pin "1") (pinfunction "+_1") (pintype "unspecified"))
    )
    (net (code "51") (name "Net-(U18-+)") (class "Default")
      (node (ref "R23") (pin "1") (pinfunction "1_1") (pintype "unspecified"))
      (node (ref "U18") (pin "1") (pinfunction "+_1") (pintype "unspecified"))
    )
    (net (code "52") (name "P_Shoot") (class "Default")
      (node (ref "H3") (pin "1") (pinfunction "1_1") (pintype "input"))
      (node (ref "U15") (pin "12") (pinfunction "IO27_12") (pintype "unspecified"))
    )
    (net (code "53") (name "SD_CS") (class "Default")
      (node (ref "R14") (pin "1") (pinfunction "1_1") (pintype "unspecified"))
      (node (ref "U15") (pin "29") (pinfunction "IO5_29") (pintype "unspecified"))
      (node (ref "U9") (pin "2") (pinfunction "CDDAT3(CS)_2") (pintype "bidirectional"))
    )
    (net (code "54") (name "TVC_X") (class "Default")
      (node (ref "H1") (pin "1") (pinfunction "1_1") (pintype "input"))
      (node (ref "U15") (pin "10") (pinfunction "IO25_10") (pintype "unspecified"))
    )
    (net (code "55") (name "TVC_Y") (class "Default")
      (node (ref "H2") (pin "1") (pinfunction "1_1") (pintype "input"))
      (node (ref "U15") (pin "11") (pinfunction "IO26_11") (pintype "unspecified"))
    )
    (net (code "56") (name "USB_D+") (class "Default")
      (node (ref "U8") (pin "5") (pinfunction "D+_5") (pintype "unspecified"))
      (node (ref "USB1") (pin "3") (pinfunction "D+_3") (pintype "input"))
    )
    (net (code "57") (name "USB_D-") (class "Default")
      (node (ref "U8") (pin "6") (pinfunction "D-_6") (pintype "unspecified"))
      (node (ref "USB1") (pin "2") (pinfunction "D-_2") (pintype "input"))
    )
    (net (code "58") (name "USB_VCC") (class "Default")
      (node (ref "C15") (pin "1") (pinfunction "1_1") (pintype "input"))
      (node (ref "D2") (pin "1") (pinfunction "A_1") (pintype "unspecified"))
      (node (ref "Q4") (pin "1") (pinfunction "G_1") (pintype "unspecified"))
      (node (ref "R8") (pin "2") (pinfunction "2_2") (pintype "unspecified"))
      (node (ref "U1") (pin "4") (pinfunction "VCC_4") (pintype "unspecified"))
      (node (ref "U1") (pin "8") (pinfunction "CE_8") (pintype "unspecified"))
      (node (ref "U4") (pin "1") (pinfunction "+_1") (pintype "unspecified"))
      (node (ref "U5") (pin "1") (pinfunction "+_1") (pintype "unspecified"))
      (node (ref "U8") (pin "16") (pinfunction "VCC_16") (pintype "unspecified"))
      (node (ref "USB1") (pin "1") (pinfunction "VBUS_1") (pintype "input"))
    )
    (net (code "59") (name "V_M") (class "Default")
      (node (ref "R1") (pin "1") (pinfunction "1_1") (pintype "unspecified"))
      (node (ref "R9") (pin "2") (pinfunction "2_2") (pintype "unspecified"))
      (node (ref "U15") (pin "6") (pinfunction "IO34_6") (pintype "unspecified"))
    )
    (net (code "60") (name "unconnected-(Q1-D12-Pad2)") (class "Default")
      (node (ref "Q1") (pin "2") (pinfunction "D12_2") (pintype "unspecified"))
    )
    (net (code "61") (name "unconnected-(Q1-D12-Pad5)") (class "Default")
      (node (ref "Q1") (pin "5") (pinfunction "D12_5") (pintype "unspecified"))
    )
    (net (code "62") (name "unconnected-(SW1-Pad3)") (class "Default")
      (node (ref "SW1") (pin "3") (pinfunction "3_3") (pintype "unspecified"))
    )
    (net (code "63") (name "unconnected-(U1-EP-Pad9)") (class "Default")
      (node (ref "U1") (pin "9") (pinfunction "EP_9") (pintype "unspecified"))
    )
    (net (code "64") (name "unconnected-(U2-TD-Pad4)") (class "Default")
      (node (ref "U2") (pin "4") (pinfunction "TD_4") (pintype "unspecified"))
    )
    (net (code "65") (name "unconnected-(U3-NC-Pad6)") (class "Default")
      (node (ref "U3") (pin "6") (pinfunction "NC_6") (pintype "unspecified"))
    )
    (net (code "66") (name "unconnected-(U6-Vout-Pad4)") (class "Default")
      (node (ref "U6") (pin "4") (pinfunction "Vout_4") (pintype "unspecified"))
    )
    (net (code "67") (name "unconnected-(U8-CTS#-Pad9)") (class "Default")
      (node (ref "U8") (pin "9") (pinfunction "CTS#_9") (pintype "unspecified"))
    )
    (net (code "68") (name "unconnected-(U8-DCD#-Pad12)") (class "Default")
      (node (ref "U8") (pin "12") (pinfunction "DCD#_12") (pintype "unspecified"))
    )
    (net (code "69") (name "unconnected-(U8-DSR#-Pad10)") (class "Default")
      (node (ref "U8") (pin "10") (pinfunction "DSR#_10") (pintype "unspecified"))
    )
    (net (code "70") (name "unconnected-(U8-NC.-Pad7)") (class "Default")
      (node (ref "U8") (pin "7") (pinfunction "NC._7") (pintype "unspecified"))
    )
    (net (code "71") (name "unconnected-(U8-NC.-Pad8)") (class "Default")
      (node (ref "U8") (pin "8") (pinfunction "NC._8") (pintype "unspecified"))
    )
    (net (code "72") (name "unconnected-(U8-R232-Pad15)") (class "Default")
      (node (ref "U8") (pin "15") (pinfunction "R232_15") (pintype "unspecified"))
    )
    (net (code "73") (name "unconnected-(U8-RI#-Pad11)") (class "Default")
      (node (ref "U8") (pin "11") (pinfunction "RI#_11") (pintype "unspecified"))
    )
    (net (code "74") (name "unconnected-(U9-CD-Pad9)") (class "Default")
      (node (ref "U9") (pin "9") (pinfunction "CD_9") (pintype "input"))
    )
    (net (code "75") (name "unconnected-(U9-DAT1(RSV)-Pad8)") (class "Default")
      (node (ref "U9") (pin "8") (pinfunction "DAT1(RSV)_8") (pintype "bidirectional"))
    )
    (net (code "76") (name "unconnected-(U9-DAT2(RSV)-Pad1)") (class "Default")
      (node (ref "U9") (pin "1") (pinfunction "DAT2(RSV)_1") (pintype "bidirectional"))
    )
    (net (code "77") (name "unconnected-(U10-AUX_CL-Pad7)") (class "Default")
      (node (ref "U10") (pin "7") (pinfunction "AUX_CL_7") (pintype "unspecified"))
    )
    (net (code "78") (name "unconnected-(U10-AUX_DA-Pad6)") (class "Default")
      (node (ref "U10") (pin "6") (pinfunction "AUX_DA_6") (pintype "unspecified"))
    )
    (net (code "79") (name "unconnected-(U10-INT-Pad12)") (class "Default")
      (node (ref "U10") (pin "12") (pinfunction "INT_12") (pintype "unspecified"))
    )
    (net (code "80") (name "unconnected-(U10-NC-Pad2)") (class "Default")
      (node (ref "U10") (pin "2") (pinfunction "NC_2") (pintype "unspecified"))
    )
    (net (code "81") (name "unconnected-(U10-NC-Pad3)") (class "Default")
      (node (ref "U10") (pin "3") (pinfunction "NC_3") (pintype "unspecified"))
    )
    (net (code "82") (name "unconnected-(U10-NC-Pad4)") (class "Default")
      (node (ref "U10") (pin "4") (pinfunction "NC_4") (pintype "unspecified"))
    )
    (net (code "83") (name "unconnected-(U10-NC-Pad5)") (class "Default")
      (node (ref "U10") (pin "5") (pinfunction "NC_5") (pintype "unspecified"))
    )
    (net (code "84") (name "unconnected-(U10-NC-Pad14)") (class "Default")
      (node (ref "U10") (pin "14") (pinfunction "NC_14") (pintype "unspecified"))
    )
    (net (code "85") (name "unconnected-(U10-NC-Pad15)") (class "Default")
      (node (ref "U10") (pin "15") (pinfunction "NC_15") (pintype "unspecified"))
    )
    (net (code "86") (name "unconnected-(U10-NC-Pad16)") (class "Default")
      (node (ref "U10") (pin "16") (pinfunction "NC_16") (pintype "unspecified"))
    )
    (net (code "87") (name "unconnected-(U10-NC-Pad17)") (class "Default")
      (node (ref "U10") (pin "17") (pinfunction "NC_17") (pintype "unspecified"))
    )
    (net (code "88") (name "unconnected-(U10-RESV-Pad19)") (class "Default")
      (node (ref "U10") (pin "19") (pinfunction "RESV_19") (pintype "unspecified"))
    )
    (net (code "89") (name "unconnected-(U10-RESV-Pad21)") (class "Default")
      (node (ref "U10") (pin "21") (pinfunction "RESV_21") (pintype "unspecified"))
    )
    (net (code "90") (name "unconnected-(U10-RESV-Pad22)") (class "Default")
      (node (ref "U10") (pin "22") (pinfunction "RESV_22") (pintype "unspecified"))
    )
    (net (code "91") (name "unconnected-(U11-DRDY-Pad15)") (class "Default")
      (node (ref "U11") (pin "15") (pinfunction "DRDY_15") (pintype "unspecified"))
    )
    (net (code "92") (name "unconnected-(U11-NC-Pad3)") (class "Default")
      (node (ref "U11") (pin "3") (pinfunction "NC_3") (pintype "unspecified"))
    )
    (net (code "93") (name "unconnected-(U11-NC-Pad5)") (class "Default")
      (node (ref "U11") (pin "5") (pinfunction "NC_5") (pintype "unspecified"))
    )
    (net (code "94") (name "unconnected-(U11-NC-Pad6)") (class "Default")
      (node (ref "U11") (pin "6") (pinfunction "NC_6") (pintype "unspecified"))
    )
    (net (code "95") (name "unconnected-(U11-NC-Pad7)") (class "Default")
      (node (ref "U11") (pin "7") (pinfunction "NC_7") (pintype "unspecified"))
    )
    (net (code "96") (name "unconnected-(U11-NC-Pad14)") (class "Default")
      (node (ref "U11") (pin "14") (pinfunction "NC_14") (pintype "unspecified"))
    )
    (net (code "97") (name "unconnected-(U13-CSB-Pad1)") (class "Default")
      (node (ref "U13") (pin "1") (pinfunction "CSB_1") (pintype "unspecified"))
    )
    (net (code "98") (name "unconnected-(U13-SDO-Pad4)") (class "Default")
      (node (ref "U13") (pin "4") (pinfunction "SDO_4") (pintype "unspecified"))
    )
    (net (code "99") (name "unconnected-(U15-CLK-Pad20)") (class "Default")
      (node (ref "U15") (pin "20") (pinfunction "CLK_20") (pintype "unspecified"))
    )
    (net (code "100") (name "unconnected-(U15-CMD-Pad19)") (class "Default")
      (node (ref "U15") (pin "19") (pinfunction "CMD_19") (pintype "unspecified"))
    )
    (net (code "101") (name "unconnected-(U15-IO12-Pad14)") (class "Default")
      (node (ref "U15") (pin "14") (pinfunction "IO12_14") (pintype "unspecified"))
    )
    (net (code "102") (name "unconnected-(U15-IO14-Pad13)") (class "Default")
      (node (ref "U15") (pin "13") (pinfunction "IO14_13") (pintype "unspecified"))
    )
    (net (code "103") (name "unconnected-(U15-IO15-Pad23)") (class "Default")
      (node (ref "U15") (pin "23") (pinfunction "IO15_23") (pintype "unspecified"))
    )
    (net (code "104") (name "unconnected-(U15-IO16-Pad27)") (class "Default")
      (node (ref "U15") (pin "27") (pinfunction "IO16_27") (pintype "unspecified"))
    )
    (net (code "105") (name "unconnected-(U15-IO17-Pad28)") (class "Default")
      (node (ref "U15") (pin "28") (pinfunction "IO17_28") (pintype "unspecified"))
    )
    (net (code "106") (name "unconnected-(U15-IO35-Pad7)") (class "Default")
      (node (ref "U15") (pin "7") (pinfunction "IO35_7") (pintype "unspecified"))
    )
    (net (code "107") (name "unconnected-(U15-NC-Pad32)") (class "Default")
      (node (ref "U15") (pin "32") (pinfunction "NC_32") (pintype "unspecified"))
    )
    (net (code "108") (name "unconnected-(U15-SD0-Pad21)") (class "Default")
      (node (ref "U15") (pin "21") (pinfunction "SD0_21") (pintype "unspecified"))
    )
    (net (code "109") (name "unconnected-(U15-SD1-Pad22)") (class "Default")
      (node (ref "U15") (pin "22") (pinfunction "SD1_22") (pintype "unspecified"))
    )
    (net (code "110") (name "unconnected-(U15-SD2-Pad17)") (class "Default")
      (node (ref "U15") (pin "17") (pinfunction "SD2_17") (pintype "unspecified"))
    )
    (net (code "111") (name "unconnected-(U15-SD3-Pad18)") (class "Default")
      (node (ref "U15") (pin "18") (pinfunction "SD3_18") (pintype "unspecified"))
    )
    (net (code "112") (name "unconnected-(U15-SENSOR_VN-Pad5)") (class "Default")
      (node (ref "U15") (pin "5") (pinfunction "SENSOR_VN_5") (pintype "unspecified"))
    )
    (net (code "113") (name "unconnected-(U15-SENSOR_VP-Pad4)") (class "Default")
      (node (ref "U15") (pin "4") (pinfunction "SENSOR_VP_4") (pintype "unspecified"))
    )
    (net (code "114") (name "unconnected-(USB1-EH-Pad6)") (class "Default")
      (node (ref "USB1") (pin "6") (pinfunction "EH_6") (pintype "input"))
    )
    (net (code "115") (name "unconnected-(USB1-ID-Pad4)") (class "Default")
      (node (ref "USB1") (pin "4") (pinfunction "ID_4") (pintype "input"))
    )
  )
)
